# Communication_Interface.net
KiCad netlist of a schematic drawn in Altium Designer
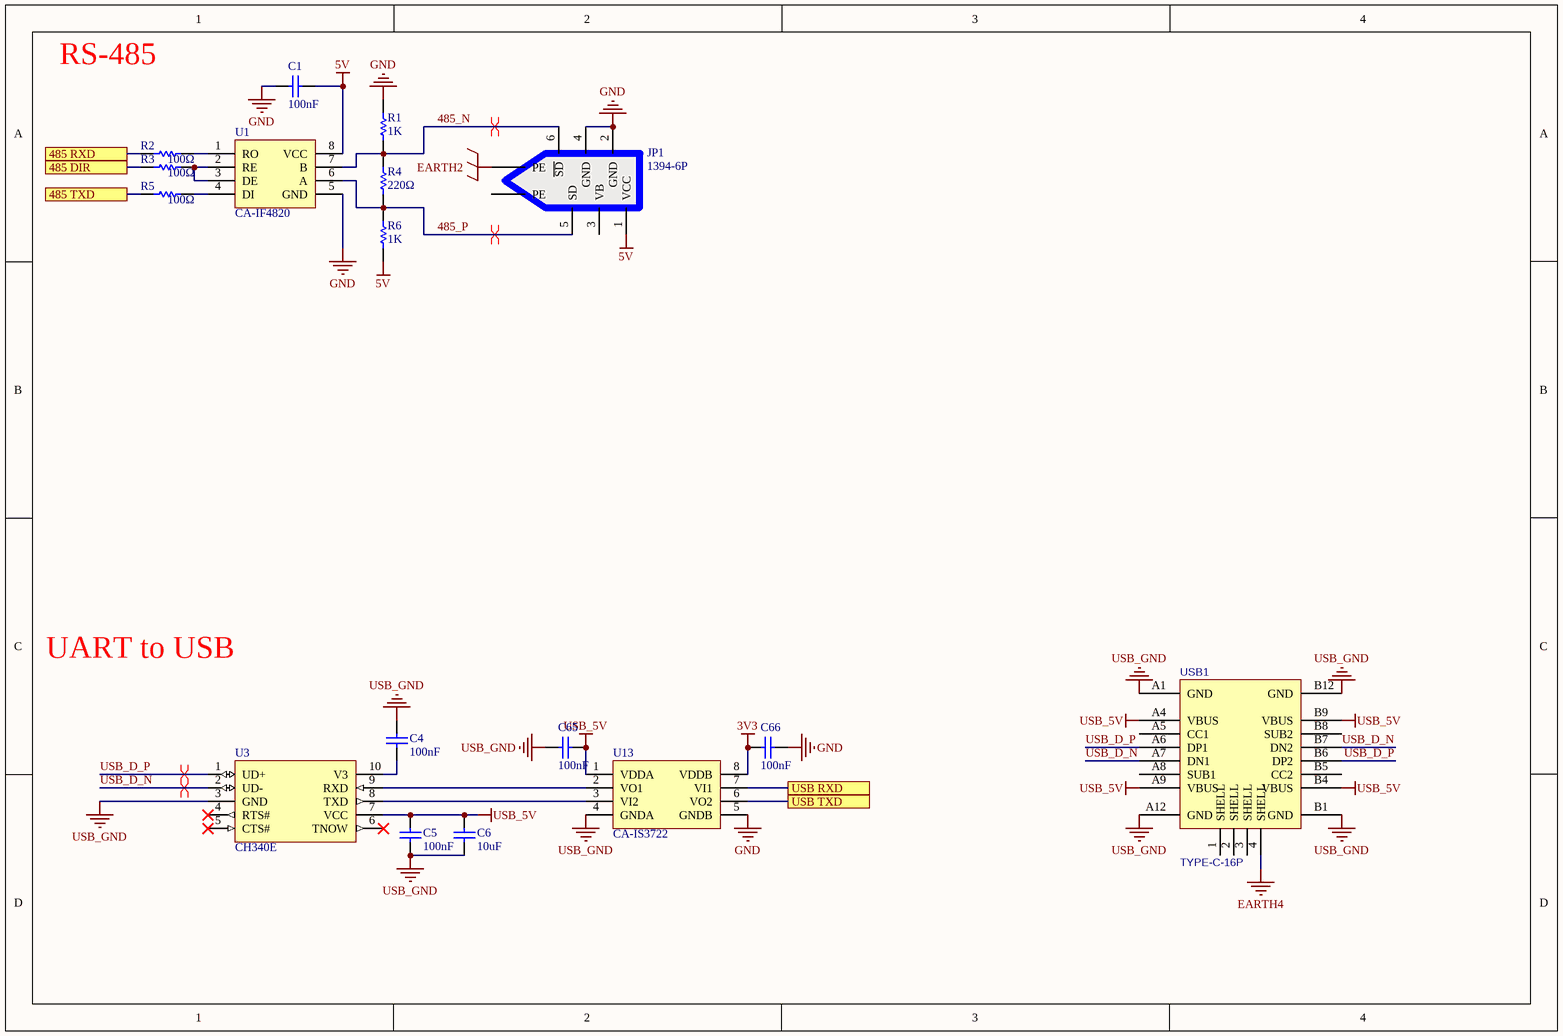
[diagram p0: Communication Interface.SchDoc]

(export (version "E")
  (design (tool "Eeschema 10.0.6"))
  (components
    (comp (ref "C1") (value "100nF") (footprint "C0603") (libsource (lib "Cap") (part "Cap")))
    (comp (ref "C4") (value "100nF") (footprint "C0603") (libsource (lib "Cap") (part "Cap_100nF")))
    (comp (ref "C5") (value "100nF") (footprint "C0603") (libsource (lib "Cap") (part "Cap_100nF")))
    (comp (ref "C6") (value "10uF") (footprint "C0603") (libsource (lib "Cap") (part "Cap")))
    (comp (ref "C65") (value "100nF") (footprint "C0603") (libsource (lib "Cap") (part "Cap_100nF")))
    (comp (ref "C66") (value "100nF") (footprint "C0603") (libsource (lib "Cap") (part "Cap_100nF")))
    (comp (ref "JP1")
      (value "1394-6P")
      (footprint "1394-6P")
      (description "IEEE 1394 FireWire接口")
      (libsource (lib "All lib") (part "1394-6P"))
    )
    (comp (ref "R1") (value "1K") (footprint "R0603") (libsource (lib "Res") (part "RES")))
    (comp (ref "R2") (value "100Ω") (footprint "R0603") (libsource (lib "Res") (part "RES")))
    (comp (ref "R3") (value "100Ω") (footprint "R0603") (libsource (lib "Res") (part "RES")))
    (comp (ref "R4") (value "220Ω") (footprint "R0603") (libsource (lib "Res") (part "RES")))
    (comp (ref "R5") (value "100Ω") (footprint "R0603") (libsource (lib "Res") (part "RES")))
    (comp (ref "R6") (value "1K") (footprint "R0603") (libsource (lib "Res") (part "RES")))
    (comp (ref "U1")
      (value "CA-IF4820")
      (footprint "SOP8_N")
      (description "485总线芯片")
      (libsource (lib "All lib") (part "CA-IF4820"))
    )
    (comp (ref "U3")
      (value "CH340E")
      (footprint "MSOP10")
      (description "USB to TTL Serial / UART")
      (libsource (lib "All lib") (part "CH340E"))
    )
    (comp (ref "U13")
      (value "CA-IS3722")
      (footprint "SOIC8_L W=3.9mm")
      (description "隔离芯片")
      (libsource (lib "All lib") (part "CA-IS3722"))
    )
    (comp (ref "USB1")
      (value "TYPE-C-16P")
      (footprint "USB-C_16P")
      (fields
        (field (name "BOM_SUPPLIER PART") "C709357")
        (field (name "BOM_MANUFACTURER PART") "KH-TYPE-C-16P")
        (field (name "CONTRIBUTOR") "LCSC")
      )
      (libsource (lib "All lib") (part "USB-C-16P"))
    )
  )
  (nets
    (net (code "1") (name "/485 DIR") (class "Default")
      (node (ref "R3") (pin "1") (pinfunction "1_1") (pintype "passive"))
    )
    (net (code "2") (name "/485 RXD") (class "Default")
      (node (ref "R2") (pin "1") (pinfunction "1_1") (pintype "passive"))
    )
    (net (code "3") (name "/485 TXD") (class "Default")
      (node (ref "R5") (pin "1") (pinfunction "1_1") (pintype "passive"))
    )
    (net (code "4") (name "/485_N") (class "Default")
      (node (ref "JP1") (pin "6") (pinfunction "~{SD}_6") (pintype "passive"))
      (node (ref "R1") (pin "1") (pinfunction "1_1") (pintype "passive"))
      (node (ref "R4") (pin "2") (pinfunction "2_2") (pintype "passive"))
      (node (ref "U1") (pin "7") (pinfunction "B_7") (pintype "passive"))
    )
    (net (code "5") (name "/485_P") (class "Default")
      (node (ref "JP1") (pin "5") (pinfunction "SD_5") (pintype "passive"))
      (node (ref "R4") (pin "1") (pinfunction "1_1") (pintype "passive"))
      (node (ref "R6") (pin "2") (pinfunction "2_2") (pintype "passive"))
      (node (ref "U1") (pin "6") (pinfunction "A_6") (pintype "passive"))
    )
    (net (code "6") (name "/USB RXD") (class "Default")
      (node (ref "U13") (pin "7") (pinfunction "VI1_7") (pintype "passive"))
    )
    (net (code "7") (name "/USB TXD") (class "Default")
      (node (ref "U13") (pin "6") (pinfunction "VO2_6") (pintype "passive"))
    )
    (net (code "8") (name "/USB_D_N") (class "Default")
      (node (ref "U3") (pin "2") (pinfunction "UD-_2") (pintype "bidirectional"))
      (node (ref "USB1") (pin "A7") (pinfunction "DN1_A7") (pintype "passive"))
      (node (ref "USB1") (pin "B7") (pinfunction "DN2_B7") (pintype "passive"))
    )
    (net (code "9") (name "/USB_D_P") (class "Default")
      (node (ref "U3") (pin "1") (pinfunction "UD+_1") (pintype "bidirectional"))
      (node (ref "USB1") (pin "A6") (pinfunction "DP1_A6") (pintype "passive"))
      (node (ref "USB1") (pin "B6") (pinfunction "DP2_B6") (pintype "passive"))
    )
    (net (code "10") (name "3V3") (class "Default")
      (node (ref "C66") (pin "1") (pinfunction "1_1") (pintype "passive"))
      (node (ref "U13") (pin "8") (pinfunction "VDDB_8") (pintype "passive"))
    )
    (net (code "11") (name "5V") (class "Default")
      (node (ref "C1") (pin "2") (pinfunction "2_2") (pintype "passive"))
      (node (ref "JP1") (pin "1") (pinfunction "VCC_1") (pintype "passive"))
      (node (ref "R6") (pin "1") (pinfunction "1_1") (pintype "passive"))
      (node (ref "U1") (pin "8") (pinfunction "VCC_8") (pintype "passive"))
    )
    (net (code "12") (name "EARTH2") (class "Default")
      (node (ref "JP1") (pin "7") (pinfunction "PE_7") (pintype "passive"))
    )
    (net (code "13") (name "EARTH4") (class "Default")
      (node (ref "USB1") (pin "4") (pinfunction "SHELL_4") (pintype "passive"))
    )
    (net (code "14") (name "GND") (class "Default")
      (node (ref "C1") (pin "1") (pinfunction "1_1") (pintype "passive"))
      (node (ref "C66") (pin "2") (pinfunction "2_2") (pintype "passive"))
      (node (ref "JP1") (pin "2") (pinfunction "GND_2") (pintype "passive"))
      (node (ref "JP1") (pin "4") (pinfunction "GND_4") (pintype "passive"))
      (node (ref "R1") (pin "2") (pinfunction "2_2") (pintype "passive"))
      (node (ref "U1") (pin "5") (pinfunction "GND_5") (pintype "passive"))
      (node (ref "U13") (pin "5") (pinfunction "GNDB_5") (pintype "passive"))
    )
    (net (code "15") (name "Net-(U1-DE)") (class "Default")
      (node (ref "R3") (pin "2") (pinfunction "2_2") (pintype "passive"))
      (node (ref "U1") (pin "2") (pinfunction "RE_2") (pintype "passive"))
      (node (ref "U1") (pin "3") (pinfunction "DE_3") (pintype "passive"))
    )
    (net (code "16") (name "Net-(U1-DI)") (class "Default")
      (node (ref "R5") (pin "2") (pinfunction "2_2") (pintype "passive"))
      (node (ref "U1") (pin "4") (pinfunction "DI_4") (pintype "passive"))
    )
    (net (code "17") (name "Net-(U1-RO)") (class "Default")
      (node (ref "R2") (pin "2") (pinfunction "2_2") (pintype "passive"))
      (node (ref "U1") (pin "1") (pinfunction "RO_1") (pintype "passive"))
    )
    (net (code "18") (name "Net-(U3-V3)") (class "Default")
      (node (ref "C4") (pin "1") (pinfunction "1_1") (pintype "passive"))
      (node (ref "U3") (pin "10") (pinfunction "V3_10") (pintype "power_in"))
    )
    (net (code "19") (name "Net-(U13-VI2)") (class "Default")
      (node (ref "U13") (pin "3") (pinfunction "VI2_3") (pintype "passive"))
      (node (ref "U3") (pin "8") (pinfunction "TXD_8") (pintype "output"))
    )
    (net (code "20") (name "Net-(U13-VO1)") (class "Default")
      (node (ref "U13") (pin "2") (pinfunction "VO1_2") (pintype "passive"))
      (node (ref "U3") (pin "9") (pinfunction "RXD_9") (pintype "input"))
    )
    (net (code "21") (name "USB_5V") (class "Default")
      (node (ref "C5") (pin "1") (pinfunction "1_1") (pintype "passive"))
      (node (ref "C6") (pin "1") (pinfunction "1_1") (pintype "passive"))
      (node (ref "C65") (pin "2") (pinfunction "2_2") (pintype "passive"))
      (node (ref "U13") (pin "1") (pinfunction "VDDA_1") (pintype "passive"))
      (node (ref "U3") (pin "7") (pinfunction "VCC_7") (pintype "power_in"))
      (node (ref "USB1") (pin "A4") (pinfunction "VBUS_A4") (pintype "passive"))
      (node (ref "USB1") (pin "A9") (pinfunction "VBUS_A9") (pintype "passive"))
      (node (ref "USB1") (pin "B4") (pinfunction "VBUS_B4") (pintype "passive"))
      (node (ref "USB1") (pin "B9") (pinfunction "VBUS_B9") (pintype "passive"))
    )
    (net (code "22") (name "USB_GND") (class "Default")
      (node (ref "C4") (pin "2") (pinfunction "2_2") (pintype "passive"))
      (node (ref "C5") (pin "2") (pinfunction "2_2") (pintype "passive"))
      (node (ref "C6") (pin "2") (pinfunction "2_2") (pintype "passive"))
      (node (ref "C65") (pin "1") (pinfunction "1_1") (pintype "passive"))
      (node (ref "U13") (pin "4") (pinfunction "GNDA_4") (pintype "passive"))
      (node (ref "U3") (pin "3") (pinfunction "GND_3") (pintype "power_in"))
      (node (ref "USB1") (pin "A1") (pinfunction "GND_A1") (pintype "passive"))
      (node (ref "USB1") (pin "A12") (pinfunction "GND_A12") (pintype "passive"))
      (node (ref "USB1") (pin "B1") (pinfunction "GND_B1") (pintype "passive"))
      (node (ref "USB1") (pin "B12") (pinfunction "GND_B12") (pintype "passive"))
    )
    (net (code "23") (name "unconnected-(JP1-PE-Pad8)") (class "Default")
      (node (ref "JP1") (pin "8") (pinfunction "PE_8") (pintype "passive"))
    )
    (net (code "24") (name "unconnected-(JP1-VB-Pad3)") (class "Default")
      (node (ref "JP1") (pin "3") (pinfunction "VB_3") (pintype "passive"))
    )
    (net (code "25") (name "unconnected-(U3-CTS#-Pad5)") (class "Default")
      (node (ref "U3") (pin "5") (pinfunction "CTS#_5") (pintype "input+no_connect"))
    )
    (net (code "26") (name "unconnected-(U3-RTS#-Pad4)") (class "Default")
      (node (ref "U3") (pin "4") (pinfunction "RTS#_4") (pintype "output+no_connect"))
    )
    (net (code "27") (name "unconnected-(U3-TNOW-Pad6)") (class "Default")
      (node (ref "U3") (pin "6") (pinfunction "TNOW_6") (pintype "output+no_connect"))
    )
    (net (code "28") (name "unconnected-(USB1-CC1-PadA5)") (class "Default")
      (node (ref "USB1") (pin "A5") (pinfunction "CC1_A5") (pintype "passive"))
    )
    (net (code "29") (name "unconnected-(USB1-CC2-PadB5)") (class "Default")
      (node (ref "USB1") (pin "B5") (pinfunction "CC2_B5") (pintype "passive"))
    )
    (net (code "30") (name "unconnected-(USB1-SHELL-Pad1)") (class "Default")
      (node (ref "USB1") (pin "1") (pinfunction "SHELL_1") (pintype "passive"))
    )
    (net (code "31") (name "unconnected-(USB1-SHELL-Pad2)") (class "Default")
      (node (ref "USB1") (pin "2") (pinfunction "SHELL_2") (pintype "passive"))
    )
    (net (code "32") (name "unconnected-(USB1-SHELL-Pad3)") (class "Default")
      (node (ref "USB1") (pin "3") (pinfunction "SHELL_3") (pintype "passive"))
    )
    (net (code "33") (name "unconnected-(USB1-SUB1-PadA8)") (class "Default")
      (node (ref "USB1") (pin "A8") (pinfunction "SUB1_A8") (pintype "passive"))
    )
    (net (code "34") (name "unconnected-(USB1-SUB2-PadB8)") (class "Default")
      (node (ref "USB1") (pin "B8") (pinfunction "SUB2_B8") (pintype "passive"))
    )
  )
)
